# hkr3000.net
KiCad netlist of a schematic drawn in EAGLE
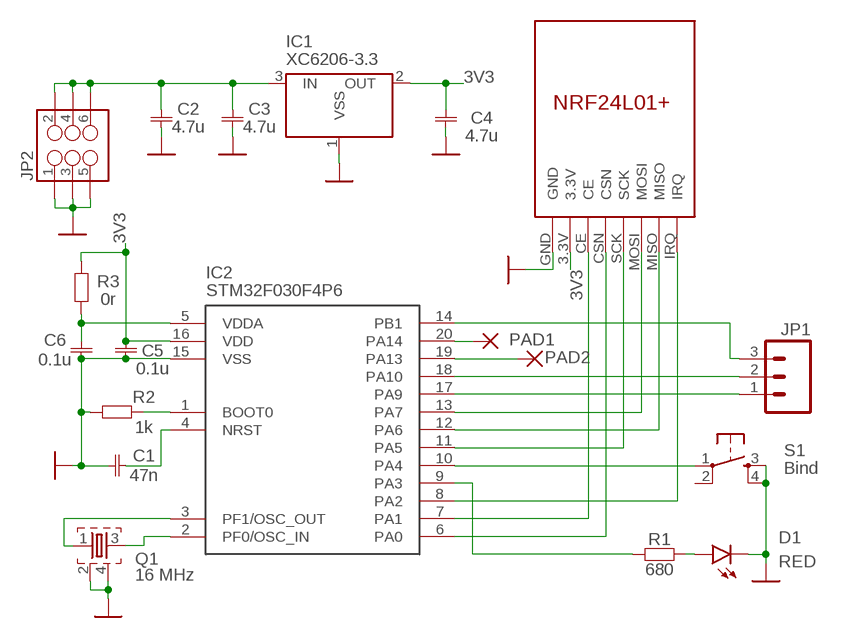
[diagram p0: schematic, sheet 1]

(export (version "E")
  (design (tool "Eeschema 10.0.6"))
  (components
    (comp (ref "C1")
      (value "47n")
      (footprint "eagle-import:0402")
      (libsource (lib "eagle-import") (part "C0402"))
    )
    (comp (ref "C2")
      (value "4.7u")
      (footprint "eagle-import:0805")
      (libsource (lib "eagle-import") (part "C0805"))
    )
    (comp (ref "C3")
      (value "4.7u")
      (footprint "eagle-import:0805")
      (libsource (lib "eagle-import") (part "C0805"))
    )
    (comp (ref "C4")
      (value "4.7u")
      (footprint "eagle-import:0805")
      (libsource (lib "eagle-import") (part "C0805"))
    )
    (comp (ref "C5")
      (value "0.1u")
      (footprint "eagle-import:0402")
      (libsource (lib "eagle-import") (part "C0402"))
    )
    (comp (ref "C6")
      (value "0.1u")
      (footprint "eagle-import:0402")
      (libsource (lib "eagle-import") (part "C0402"))
    )
    (comp (ref "D1")
      (value "RED")
      (footprint "eagle-import:LED-0603")
      (libsource (lib "eagle-import") (part "LED-RED0603"))
    )
    (comp (ref "IC1")
      (value "XC6206-3.3")
      (footprint "eagle-import:XC6206_SOT-23")
      (libsource (lib "eagle-import") (part "XC6206SOT-23"))
    )
    (comp (ref "IC2")
      (value "STM32F030F4P6")
      (footprint "eagle-import:TSSOP-20")
      (libsource (lib "eagle-import") (part "STM32F030XTSSOP20"))
    )
    (comp (ref "JP1")
      (value "M03PTH")
      (footprint "eagle-import:1X03")
      (libsource (lib "eagle-import") (part "M03PTH"))
    )
    (comp (ref "JP2")
      (value "M03X2POGO_PINS")
      (footprint "eagle-import:2X3_POGO")
      (libsource (lib "eagle-import") (part "M03X2POGO_PINS"))
    )
    (comp (ref "PAD1")
      (value "SMD2")
      (footprint "eagle-import:SMD1,27-2,54")
      (libsource (lib "eagle-import") (part "SMD2"))
    )
    (comp (ref "PAD2")
      (value "SMD2")
      (footprint "eagle-import:SMD1,27-2,54")
      (libsource (lib "eagle-import") (part "SMD2"))
    )
    (comp (ref "Q1")
      (value "16 MHz")
      (footprint "eagle-import:FA-20H")
      (libsource (lib "eagle-import") (part "FA-3225"))
    )
    (comp (ref "R1")
      (value "680")
      (footprint "eagle-import:0402")
      (libsource (lib "eagle-import") (part "R0402"))
    )
    (comp (ref "R2")
      (value "1k")
      (footprint "eagle-import:0402")
      (libsource (lib "eagle-import") (part "R0402"))
    )
    (comp (ref "R3")
      (value "0r")
      (footprint "eagle-import:0603")
      (libsource (lib "eagle-import") (part "R0603"))
    )
    (comp (ref "S1")
      (value "Bind")
      (footprint "eagle-import:TACTILE-PTH")
      (libsource (lib "eagle-import") (part "TAC_SWITCHPTH"))
    )
    (comp (ref "U$1")
      (value "NRF24L01")
      (footprint "eagle-import:NRF24L01")
      (libsource (lib "eagle-import") (part "NRF24L01"))
    )
  )
  (nets
    (net (code "1") (name "3V3") (class "Default")
      (node (ref "C4") (pin "P$2") (pinfunction "P$2_P$2") (pintype "passive"))
      (node (ref "C5") (pin "P$2") (pinfunction "P$2_P$2") (pintype "passive"))
      (node (ref "IC1") (pin "2") (pinfunction "OUT_2") (pintype "bidirectional"))
      (node (ref "IC2") (pin "16") (pinfunction "VDD_16") (pintype "bidirectional"))
      (node (ref "R3") (pin "P$2") (pinfunction "P$2_P$2") (pintype "passive"))
      (node (ref "U$1") (pin "3.3V") (pinfunction "3.3V_3.3V") (pintype "bidirectional"))
    )
    (net (code "2") (name "GND") (class "Default")
      (node (ref "C1") (pin "P$1") (pinfunction "P$1_P$1") (pintype "passive"))
      (node (ref "C2") (pin "P$1") (pinfunction "P$1_P$1") (pintype "passive"))
      (node (ref "C3") (pin "P$1") (pinfunction "P$1_P$1") (pintype "passive"))
      (node (ref "C4") (pin "P$1") (pinfunction "P$1_P$1") (pintype "passive"))
      (node (ref "C5") (pin "P$1") (pinfunction "P$1_P$1") (pintype "passive"))
      (node (ref "C6") (pin "P$1") (pinfunction "P$1_P$1") (pintype "passive"))
      (node (ref "D1") (pin "C") (pinfunction "C_C") (pintype "passive"))
      (node (ref "IC1") (pin "1") (pinfunction "VSS_1") (pintype "bidirectional"))
      (node (ref "IC2") (pin "15") (pinfunction "VSS_15") (pintype "bidirectional"))
      (node (ref "JP2") (pin "P$1") (pinfunction "1_P$1") (pintype "bidirectional"))
      (node (ref "JP2") (pin "P$3") (pinfunction "3_P$3") (pintype "bidirectional"))
      (node (ref "JP2") (pin "P$5") (pinfunction "5_P$5") (pintype "bidirectional"))
      (node (ref "Q1") (pin "2") (pinfunction "2_2") (pintype "passive"))
      (node (ref "Q1") (pin "4") (pinfunction "4_4") (pintype "passive"))
      (node (ref "R2") (pin "P$1") (pinfunction "P$1_P$1") (pintype "passive"))
      (node (ref "S1") (pin "3") (pinfunction "3_3") (pintype "passive"))
      (node (ref "S1") (pin "4") (pinfunction "4_4") (pintype "passive"))
      (node (ref "U$1") (pin "GND") (pinfunction "GND_GND") (pintype "bidirectional"))
    )
    (net (code "3") (name "Net-(D1-PadA)") (class "Default")
      (node (ref "D1") (pin "A") (pinfunction "A_A") (pintype "passive"))
      (node (ref "R1") (pin "P$2") (pinfunction "P$2_P$2") (pintype "passive"))
    )
    (net (code "4") (name "Net-(IC1-IN)") (class "Default")
      (node (ref "C2") (pin "P$2") (pinfunction "P$2_P$2") (pintype "passive"))
      (node (ref "C3") (pin "P$2") (pinfunction "P$2_P$2") (pintype "passive"))
      (node (ref "IC1") (pin "3") (pinfunction "IN_3") (pintype "bidirectional"))
      (node (ref "JP2") (pin "P$2") (pinfunction "2_P$2") (pintype "bidirectional"))
      (node (ref "JP2") (pin "P$4") (pinfunction "4_P$4") (pintype "bidirectional"))
      (node (ref "JP2") (pin "P$6") (pinfunction "6_P$6") (pintype "bidirectional"))
    )
    (net (code "5") (name "Net-(IC2-BOOT0)") (class "Default")
      (node (ref "IC2") (pin "1") (pinfunction "BOOT0_1") (pintype "bidirectional"))
      (node (ref "R2") (pin "P$2") (pinfunction "P$2_P$2") (pintype "passive"))
    )
    (net (code "6") (name "Net-(IC2-NRST)") (class "Default")
      (node (ref "C1") (pin "P$2") (pinfunction "P$2_P$2") (pintype "passive"))
      (node (ref "IC2") (pin "4") (pinfunction "NRST_4") (pintype "bidirectional"))
    )
    (net (code "7") (name "Net-(IC2-PA0)") (class "Default")
      (node (ref "IC2") (pin "6") (pinfunction "PA0_6") (pintype "bidirectional"))
      (node (ref "U$1") (pin "CSN") (pinfunction "CSN_CSN") (pintype "bidirectional"))
    )
    (net (code "8") (name "Net-(IC2-PA1)") (class "Default")
      (node (ref "IC2") (pin "7") (pinfunction "PA1_7") (pintype "bidirectional"))
      (node (ref "U$1") (pin "CE") (pinfunction "CE_CE") (pintype "bidirectional"))
    )
    (net (code "9") (name "Net-(IC2-PA2)") (class "Default")
      (node (ref "IC2") (pin "8") (pinfunction "PA2_8") (pintype "bidirectional"))
      (node (ref "U$1") (pin "IRQ") (pinfunction "IRQ_IRQ") (pintype "bidirectional"))
    )
    (net (code "10") (name "Net-(IC2-PA3)") (class "Default")
      (node (ref "IC2") (pin "9") (pinfunction "PA3_9") (pintype "bidirectional"))
      (node (ref "R1") (pin "P$1") (pinfunction "P$1_P$1") (pintype "passive"))
    )
    (net (code "11") (name "Net-(IC2-PA4)") (class "Default")
      (node (ref "IC2") (pin "10") (pinfunction "PA4_10") (pintype "bidirectional"))
      (node (ref "S1") (pin "1") (pinfunction "1_1") (pintype "passive"))
    )
    (net (code "12") (name "Net-(IC2-PA5)") (class "Default")
      (node (ref "IC2") (pin "11") (pinfunction "PA5_11") (pintype "bidirectional"))
      (node (ref "U$1") (pin "SCK") (pinfunction "SCK_SCK") (pintype "bidirectional"))
    )
    (net (code "13") (name "Net-(IC2-PA6)") (class "Default")
      (node (ref "IC2") (pin "12") (pinfunction "PA6_12") (pintype "bidirectional"))
      (node (ref "U$1") (pin "MISO") (pinfunction "MISO_MISO") (pintype "bidirectional"))
    )
    (net (code "14") (name "Net-(IC2-PA7)") (class "Default")
      (node (ref "IC2") (pin "13") (pinfunction "PA7_13") (pintype "bidirectional"))
      (node (ref "U$1") (pin "MOSI") (pinfunction "MOSI_MOSI") (pintype "bidirectional"))
    )
    (net (code "15") (name "Net-(IC2-PA9)") (class "Default")
      (node (ref "IC2") (pin "17") (pinfunction "PA9_17") (pintype "bidirectional"))
      (node (ref "JP1") (pin "1") (pinfunction "1_1") (pintype "passive"))
    )
    (net (code "16") (name "Net-(IC2-PA10)") (class "Default")
      (node (ref "IC2") (pin "18") (pinfunction "PA10_18") (pintype "bidirectional"))
      (node (ref "JP1") (pin "2") (pinfunction "2_2") (pintype "passive"))
    )
    (net (code "17") (name "Net-(IC2-PA13)") (class "Default")
      (node (ref "IC2") (pin "19") (pinfunction "PA13_19") (pintype "bidirectional"))
      (node (ref "PAD2") (pin "1") (pinfunction "P_1") (pintype "passive"))
    )
    (net (code "18") (name "Net-(IC2-PA14)") (class "Default")
      (node (ref "IC2") (pin "20") (pinfunction "PA14_20") (pintype "bidirectional"))
      (node (ref "PAD1") (pin "1") (pinfunction "P_1") (pintype "passive"))
    )
    (net (code "19") (name "Net-(IC2-PB1)") (class "Default")
      (node (ref "IC2") (pin "14") (pinfunction "PB1_14") (pintype "bidirectional"))
      (node (ref "JP1") (pin "3") (pinfunction "3_3") (pintype "passive"))
    )
    (net (code "20") (name "Net-(IC2-PF0{slash}OSC_IN)") (class "Default")
      (node (ref "IC2") (pin "2") (pinfunction "PF0/OSC_IN_2") (pintype "bidirectional"))
      (node (ref "Q1") (pin "3") (pinfunction "3_3") (pintype "passive"))
    )
    (net (code "21") (name "Net-(IC2-PF1{slash}OSC_OUT)") (class "Default")
      (node (ref "IC2") (pin "3") (pinfunction "PF1/OSC_OUT_3") (pintype "bidirectional"))
      (node (ref "Q1") (pin "1") (pinfunction "1_1") (pintype "passive"))
    )
    (net (code "22") (name "Net-(IC2-VDDA)") (class "Default")
      (node (ref "C6") (pin "P$2") (pinfunction "P$2_P$2") (pintype "passive"))
      (node (ref "IC2") (pin "5") (pinfunction "VDDA_5") (pintype "bidirectional"))
      (node (ref "R3") (pin "P$1") (pinfunction "P$1_P$1") (pintype "passive"))
    )
    (net (code "23") (name "unconnected-(S1-Pad2)") (class "Default")
      (node (ref "S1") (pin "2") (pinfunction "2_2") (pintype "passive"))
    )
  )
)
